# Driver.net
KiCad netlist of a schematic drawn in Altium Designer
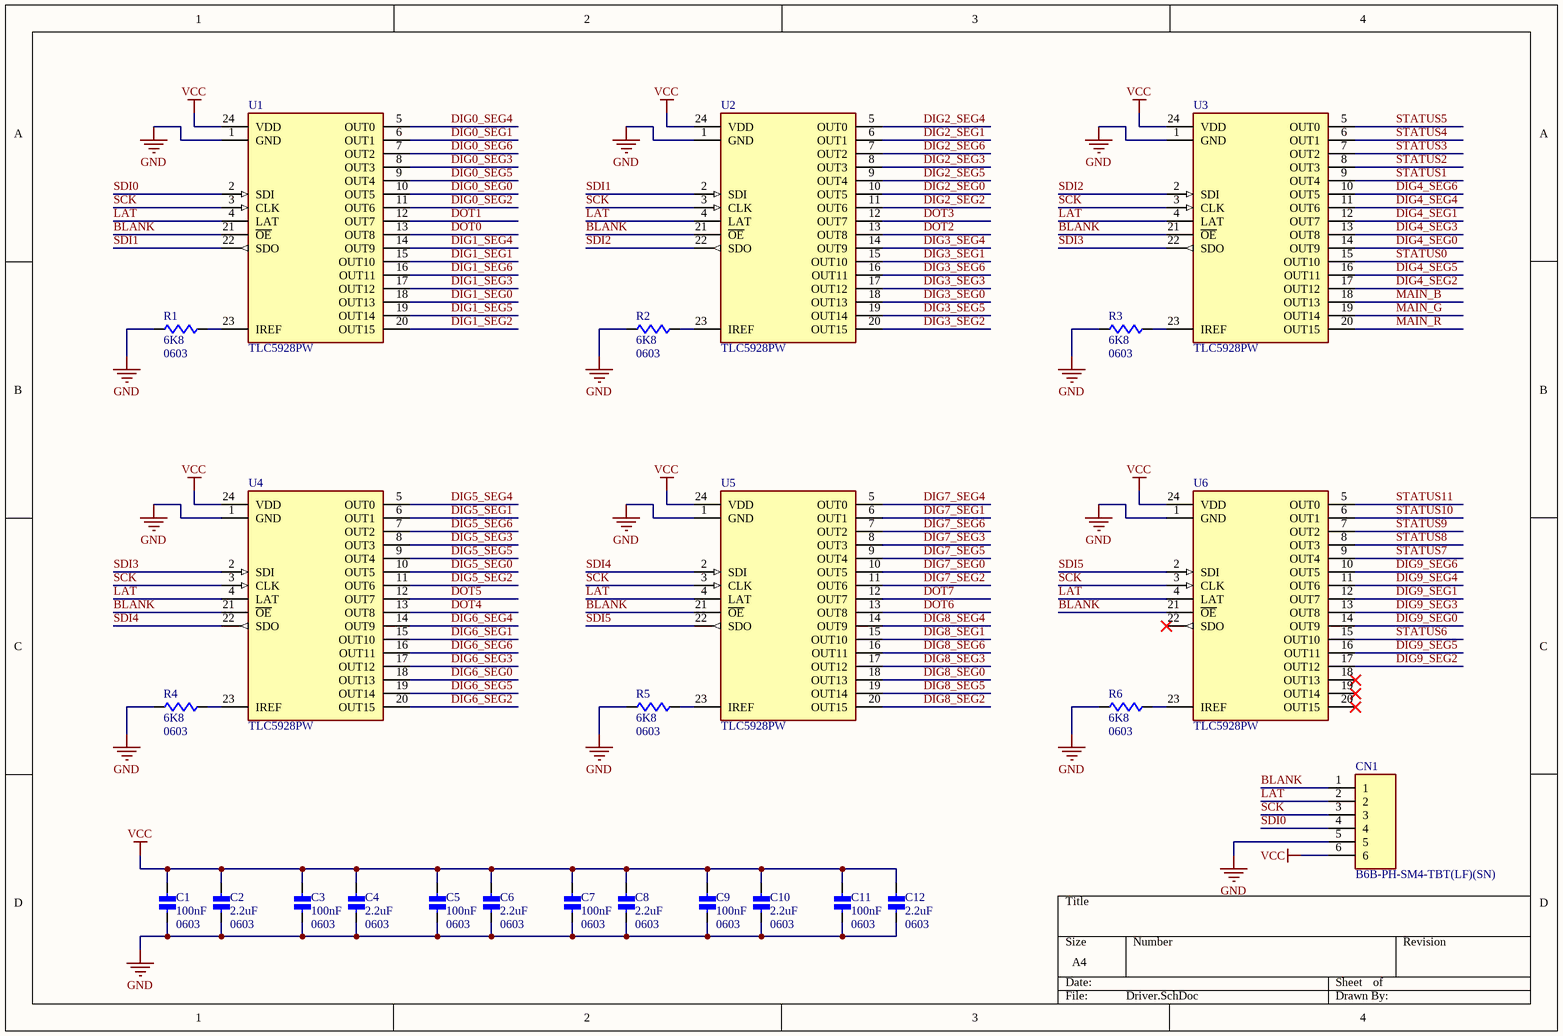
[diagram p0: Driver.SchDoc]

(export (version "E")
  (design (tool "Eeschema 10.0.6"))
  (components
    (comp (ref "C1")
      (value "100nF")
      (footprint "CAPC0603X08N")
      (description "Generic 0603 Capacitors")
      (fields (field (name "PACKAGE") "0603"))
      (libsource (lib "Chess Clock Front Display") (part "GENERIC CAPC 0603"))
    )
    (comp (ref "C2")
      (value "2.2uF")
      (footprint "CAPC0603X08N")
      (description "Generic 0603 Capacitors")
      (fields (field (name "PACKAGE") "0603"))
      (libsource (lib "Chess Clock Front Display") (part "GENERIC CAPC 0603"))
    )
    (comp (ref "C3")
      (value "100nF")
      (footprint "CAPC0603X08N")
      (description "Generic 0603 Capacitors")
      (fields (field (name "PACKAGE") "0603"))
      (libsource (lib "Chess Clock Front Display") (part "GENERIC CAPC 0603"))
    )
    (comp (ref "C4")
      (value "2.2uF")
      (footprint "CAPC0603X08N")
      (description "Generic 0603 Capacitors")
      (fields (field (name "PACKAGE") "0603"))
      (libsource (lib "Chess Clock Front Display") (part "GENERIC CAPC 0603"))
    )
    (comp (ref "C5")
      (value "100nF")
      (footprint "CAPC0603X08N")
      (description "Generic 0603 Capacitors")
      (fields (field (name "PACKAGE") "0603"))
      (libsource (lib "Chess Clock Front Display") (part "GENERIC CAPC 0603"))
    )
    (comp (ref "C6")
      (value "2.2uF")
      (footprint "CAPC0603X08N")
      (description "Generic 0603 Capacitors")
      (fields (field (name "PACKAGE") "0603"))
      (libsource (lib "Chess Clock Front Display") (part "GENERIC CAPC 0603"))
    )
    (comp (ref "C7")
      (value "100nF")
      (footprint "CAPC0603X08N")
      (description "Generic 0603 Capacitors")
      (fields (field (name "PACKAGE") "0603"))
      (libsource (lib "Chess Clock Front Display") (part "GENERIC CAPC 0603"))
    )
    (comp (ref "C8")
      (value "2.2uF")
      (footprint "CAPC0603X08N")
      (description "Generic 0603 Capacitors")
      (fields (field (name "PACKAGE") "0603"))
      (libsource (lib "Chess Clock Front Display") (part "GENERIC CAPC 0603"))
    )
    (comp (ref "C9")
      (value "100nF")
      (footprint "CAPC0603X08N")
      (description "Generic 0603 Capacitors")
      (fields (field (name "PACKAGE") "0603"))
      (libsource (lib "Chess Clock Front Display") (part "GENERIC CAPC 0603"))
    )
    (comp (ref "C10")
      (value "2.2uF")
      (footprint "CAPC0603X08N")
      (description "Generic 0603 Capacitors")
      (fields (field (name "PACKAGE") "0603"))
      (libsource (lib "Chess Clock Front Display") (part "GENERIC CAPC 0603"))
    )
    (comp (ref "C11")
      (value "100nF")
      (footprint "CAPC0603X08N")
      (description "Generic 0603 Capacitors")
      (fields (field (name "PACKAGE") "0603"))
      (libsource (lib "Chess Clock Front Display") (part "GENERIC CAPC 0603"))
    )
    (comp (ref "C12")
      (value "2.2uF")
      (footprint "CAPC0603X08N")
      (description "Generic 0603 Capacitors")
      (fields (field (name "PACKAGE") "0603"))
      (libsource (lib "Chess Clock Front Display") (part "GENERIC CAPC 0603"))
    )
    (comp (ref "CN1")
      (value "B6B-PH-SM4-TBT(LF)(SN)")
      (footprint "B6B-PH-SM4-TBT(LF)(SN)")
      (description "Connector Header Surface Mount 6 position 0.079\" (2.00mm)")
      (libsource (lib "Chess Clock Front Display") (part "B6B-PH-SM4-TBT(LF)(SN)"))
    )
    (comp (ref "R1")
      (value "6K8")
      (footprint "RESC0603X04N")
      (description "Generic 0603 1%/5% Resistor")
      (fields (field (name "PACKAGE") "0603"))
      (libsource (lib "Chess Clock Front Display") (part "GENERIC RESC 0603"))
    )
    (comp (ref "R2")
      (value "6K8")
      (footprint "RESC0603X04N")
      (description "Generic 0603 1%/5% Resistor")
      (fields (field (name "PACKAGE") "0603"))
      (libsource (lib "Chess Clock Front Display") (part "GENERIC RESC 0603"))
    )
    (comp (ref "R3")
      (value "6K8")
      (footprint "RESC0603X04N")
      (description "Generic 0603 1%/5% Resistor")
      (fields (field (name "PACKAGE") "0603"))
      (libsource (lib "Chess Clock Front Display") (part "GENERIC RESC 0603"))
    )
    (comp (ref "R4")
      (value "6K8")
      (footprint "RESC0603X04N")
      (description "Generic 0603 1%/5% Resistor")
      (fields (field (name "PACKAGE") "0603"))
      (libsource (lib "Chess Clock Front Display") (part "GENERIC RESC 0603"))
    )
    (comp (ref "R5")
      (value "6K8")
      (footprint "RESC0603X04N")
      (description "Generic 0603 1%/5% Resistor")
      (fields (field (name "PACKAGE") "0603"))
      (libsource (lib "Chess Clock Front Display") (part "GENERIC RESC 0603"))
    )
    (comp (ref "R6")
      (value "6K8")
      (footprint "RESC0603X04N")
      (description "Generic 0603 1%/5% Resistor")
      (fields (field (name "PACKAGE") "0603"))
      (libsource (lib "Chess Clock Front Display") (part "GENERIC RESC 0603"))
    )
    (comp (ref "U1")
      (value "TLC5928PW")
      (footprint "TSOP65P640X120-24N")
      (description "LED Driver IC 16 Output Linear Shift Register  Dimming 35mA 24-TSSOP")
      (fields (field (name "MANUFACTURER") "Texas Instruments"))
      (libsource (lib "Chess Clock Front Display") (part "TLC5928PW"))
    )
    (comp (ref "U2")
      (value "TLC5928PW")
      (footprint "TSOP65P640X120-24N")
      (description "LED Driver IC 16 Output Linear Shift Register  Dimming 35mA 24-TSSOP")
      (fields (field (name "MANUFACTURER") "Texas Instruments"))
      (libsource (lib "Chess Clock Front Display") (part "TLC5928PW"))
    )
    (comp (ref "U3")
      (value "TLC5928PW")
      (footprint "TSOP65P640X120-24N")
      (description "LED Driver IC 16 Output Linear Shift Register  Dimming 35mA 24-TSSOP")
      (fields (field (name "MANUFACTURER") "Texas Instruments"))
      (libsource (lib "Chess Clock Front Display") (part "TLC5928PW"))
    )
    (comp (ref "U4")
      (value "TLC5928PW")
      (footprint "TSOP65P640X120-24N")
      (description "LED Driver IC 16 Output Linear Shift Register  Dimming 35mA 24-TSSOP")
      (fields (field (name "MANUFACTURER") "Texas Instruments"))
      (libsource (lib "Chess Clock Front Display") (part "TLC5928PW"))
    )
    (comp (ref "U5")
      (value "TLC5928PW")
      (footprint "TSOP65P640X120-24N")
      (description "LED Driver IC 16 Output Linear Shift Register  Dimming 35mA 24-TSSOP")
      (fields (field (name "MANUFACTURER") "Texas Instruments"))
      (libsource (lib "Chess Clock Front Display") (part "TLC5928PW"))
    )
    (comp (ref "U6")
      (value "TLC5928PW")
      (footprint "TSOP65P640X120-24N")
      (description "LED Driver IC 16 Output Linear Shift Register  Dimming 35mA 24-TSSOP")
      (fields (field (name "MANUFACTURER") "Texas Instruments"))
      (libsource (lib "Chess Clock Front Display") (part "TLC5928PW"))
    )
  )
  (nets
    (net (code "1") (name "/BLANK") (class "Default")
      (node (ref "CN1") (pin "1") (pinfunction "1_1") (pintype "passive"))
      (node (ref "U1") (pin "21") (pinfunction "~{OE}_21") (pintype "passive"))
      (node (ref "U2") (pin "21") (pinfunction "~{OE}_21") (pintype "passive"))
      (node (ref "U3") (pin "21") (pinfunction "~{OE}_21") (pintype "passive"))
      (node (ref "U4") (pin "21") (pinfunction "~{OE}_21") (pintype "passive"))
      (node (ref "U5") (pin "21") (pinfunction "~{OE}_21") (pintype "passive"))
      (node (ref "U6") (pin "21") (pinfunction "~{OE}_21") (pintype "passive"))
    )
    (net (code "2") (name "/DIG0_SEG0") (class "Default")
      (node (ref "U1") (pin "10") (pinfunction "OUT5_10") (pintype "passive"))
    )
    (net (code "3") (name "/DIG0_SEG1") (class "Default")
      (node (ref "U1") (pin "6") (pinfunction "OUT1_6") (pintype "passive"))
    )
    (net (code "4") (name "/DIG0_SEG2") (class "Default")
      (node (ref "U1") (pin "11") (pinfunction "OUT6_11") (pintype "passive"))
    )
    (net (code "5") (name "/DIG0_SEG3") (class "Default")
      (node (ref "U1") (pin "8") (pinfunction "OUT3_8") (pintype "passive"))
    )
    (net (code "6") (name "/DIG0_SEG4") (class "Default")
      (node (ref "U1") (pin "5") (pinfunction "OUT0_5") (pintype "passive"))
    )
    (net (code "7") (name "/DIG0_SEG5") (class "Default")
      (node (ref "U1") (pin "9") (pinfunction "OUT4_9") (pintype "passive"))
    )
    (net (code "8") (name "/DIG0_SEG6") (class "Default")
      (node (ref "U1") (pin "7") (pinfunction "OUT2_7") (pintype "passive"))
    )
    (net (code "9") (name "/DIG1_SEG0") (class "Default")
      (node (ref "U1") (pin "18") (pinfunction "OUT13_18") (pintype "passive"))
    )
    (net (code "10") (name "/DIG1_SEG1") (class "Default")
      (node (ref "U1") (pin "15") (pinfunction "OUT10_15") (pintype "passive"))
    )
    (net (code "11") (name "/DIG1_SEG2") (class "Default")
      (node (ref "U1") (pin "20") (pinfunction "OUT15_20") (pintype "passive"))
    )
    (net (code "12") (name "/DIG1_SEG3") (class "Default")
      (node (ref "U1") (pin "17") (pinfunction "OUT12_17") (pintype "passive"))
    )
    (net (code "13") (name "/DIG1_SEG4") (class "Default")
      (node (ref "U1") (pin "14") (pinfunction "OUT9_14") (pintype "passive"))
    )
    (net (code "14") (name "/DIG1_SEG5") (class "Default")
      (node (ref "U1") (pin "19") (pinfunction "OUT14_19") (pintype "passive"))
    )
    (net (code "15") (name "/DIG1_SEG6") (class "Default")
      (node (ref "U1") (pin "16") (pinfunction "OUT11_16") (pintype "passive"))
    )
    (net (code "16") (name "/DIG2_SEG0") (class "Default")
      (node (ref "U2") (pin "10") (pinfunction "OUT5_10") (pintype "passive"))
    )
    (net (code "17") (name "/DIG2_SEG1") (class "Default")
      (node (ref "U2") (pin "6") (pinfunction "OUT1_6") (pintype "passive"))
    )
    (net (code "18") (name "/DIG2_SEG2") (class "Default")
      (node (ref "U2") (pin "11") (pinfunction "OUT6_11") (pintype "passive"))
    )
    (net (code "19") (name "/DIG2_SEG3") (class "Default")
      (node (ref "U2") (pin "8") (pinfunction "OUT3_8") (pintype "passive"))
    )
    (net (code "20") (name "/DIG2_SEG4") (class "Default")
      (node (ref "U2") (pin "5") (pinfunction "OUT0_5") (pintype "passive"))
    )
    (net (code "21") (name "/DIG2_SEG5") (class "Default")
      (node (ref "U2") (pin "9") (pinfunction "OUT4_9") (pintype "passive"))
    )
    (net (code "22") (name "/DIG2_SEG6") (class "Default")
      (node (ref "U2") (pin "7") (pinfunction "OUT2_7") (pintype "passive"))
    )
    (net (code "23") (name "/DIG3_SEG0") (class "Default")
      (node (ref "U2") (pin "18") (pinfunction "OUT13_18") (pintype "passive"))
    )
    (net (code "24") (name "/DIG3_SEG1") (class "Default")
      (node (ref "U2") (pin "15") (pinfunction "OUT10_15") (pintype "passive"))
    )
    (net (code "25") (name "/DIG3_SEG2") (class "Default")
      (node (ref "U2") (pin "20") (pinfunction "OUT15_20") (pintype "passive"))
    )
    (net (code "26") (name "/DIG3_SEG3") (class "Default")
      (node (ref "U2") (pin "17") (pinfunction "OUT12_17") (pintype "passive"))
    )
    (net (code "27") (name "/DIG3_SEG4") (class "Default")
      (node (ref "U2") (pin "14") (pinfunction "OUT9_14") (pintype "passive"))
    )
    (net (code "28") (name "/DIG3_SEG5") (class "Default")
      (node (ref "U2") (pin "19") (pinfunction "OUT14_19") (pintype "passive"))
    )
    (net (code "29") (name "/DIG3_SEG6") (class "Default")
      (node (ref "U2") (pin "16") (pinfunction "OUT11_16") (pintype "passive"))
    )
    (net (code "30") (name "/DIG4_SEG0") (class "Default")
      (node (ref "U3") (pin "14") (pinfunction "OUT9_14") (pintype "passive"))
    )
    (net (code "31") (name "/DIG4_SEG1") (class "Default")
      (node (ref "U3") (pin "12") (pinfunction "OUT7_12") (pintype "passive"))
    )
    (net (code "32") (name "/DIG4_SEG2") (class "Default")
      (node (ref "U3") (pin "17") (pinfunction "OUT12_17") (pintype "passive"))
    )
    (net (code "33") (name "/DIG4_SEG3") (class "Default")
      (node (ref "U3") (pin "13") (pinfunction "OUT8_13") (pintype "passive"))
    )
    (net (code "34") (name "/DIG4_SEG4") (class "Default")
      (node (ref "U3") (pin "11") (pinfunction "OUT6_11") (pintype "passive"))
    )
    (net (code "35") (name "/DIG4_SEG5") (class "Default")
      (node (ref "U3") (pin "16") (pinfunction "OUT11_16") (pintype "passive"))
    )
    (net (code "36") (name "/DIG4_SEG6") (class "Default")
      (node (ref "U3") (pin "10") (pinfunction "OUT5_10") (pintype "passive"))
    )
    (net (code "37") (name "/DIG5_SEG0") (class "Default")
      (node (ref "U4") (pin "10") (pinfunction "OUT5_10") (pintype "passive"))
    )
    (net (code "38") (name "/DIG5_SEG1") (class "Default")
      (node (ref "U4") (pin "6") (pinfunction "OUT1_6") (pintype "passive"))
    )
    (net (code "39") (name "/DIG5_SEG2") (class "Default")
      (node (ref "U4") (pin "11") (pinfunction "OUT6_11") (pintype "passive"))
    )
    (net (code "40") (name "/DIG5_SEG3") (class "Default")
      (node (ref "U4") (pin "8") (pinfunction "OUT3_8") (pintype "passive"))
    )
    (net (code "41") (name "/DIG5_SEG4") (class "Default")
      (node (ref "U4") (pin "5") (pinfunction "OUT0_5") (pintype "passive"))
    )
    (net (code "42") (name "/DIG5_SEG5") (class "Default")
      (node (ref "U4") (pin "9") (pinfunction "OUT4_9") (pintype "passive"))
    )
    (net (code "43") (name "/DIG5_SEG6") (class "Default")
      (node (ref "U4") (pin "7") (pinfunction "OUT2_7") (pintype "passive"))
    )
    (net (code "44") (name "/DIG6_SEG0") (class "Default")
      (node (ref "U4") (pin "18") (pinfunction "OUT13_18") (pintype "passive"))
    )
    (net (code "45") (name "/DIG6_SEG1") (class "Default")
      (node (ref "U4") (pin "15") (pinfunction "OUT10_15") (pintype "passive"))
    )
    (net (code "46") (name "/DIG6_SEG2") (class "Default")
      (node (ref "U4") (pin "20") (pinfunction "OUT15_20") (pintype "passive"))
    )
    (net (code "47") (name "/DIG6_SEG3") (class "Default")
      (node (ref "U4") (pin "17") (pinfunction "OUT12_17") (pintype "passive"))
    )
    (net (code "48") (name "/DIG6_SEG4") (class "Default")
      (node (ref "U4") (pin "14") (pinfunction "OUT9_14") (pintype "passive"))
    )
    (net (code "49") (name "/DIG6_SEG5") (class "Default")
      (node (ref "U4") (pin "19") (pinfunction "OUT14_19") (pintype "passive"))
    )
    (net (code "50") (name "/DIG6_SEG6") (class "Default")
      (node (ref "U4") (pin "16") (pinfunction "OUT11_16") (pintype "passive"))
    )
    (net (code "51") (name "/DIG7_SEG0") (class "Default")
      (node (ref "U5") (pin "10") (pinfunction "OUT5_10") (pintype "passive"))
    )
    (net (code "52") (name "/DIG7_SEG1") (class "Default")
      (node (ref "U5") (pin "6") (pinfunction "OUT1_6") (pintype "passive"))
    )
    (net (code "53") (name "/DIG7_SEG2") (class "Default")
      (node (ref "U5") (pin "11") (pinfunction "OUT6_11") (pintype "passive"))
    )
    (net (code "54") (name "/DIG7_SEG3") (class "Default")
      (node (ref "U5") (pin "8") (pinfunction "OUT3_8") (pintype "passive"))
    )
    (net (code "55") (name "/DIG7_SEG4") (class "Default")
      (node (ref "U5") (pin "5") (pinfunction "OUT0_5") (pintype "passive"))
    )
    (net (code "56") (name "/DIG7_SEG5") (class "Default")
      (node (ref "U5") (pin "9") (pinfunction "OUT4_9") (pintype "passive"))
    )
    (net (code "57") (name "/DIG7_SEG6") (class "Default")
      (node (ref "U5") (pin "7") (pinfunction "OUT2_7") (pintype "passive"))
    )
    (net (code "58") (name "/DIG8_SEG0") (class "Default")
      (node (ref "U5") (pin "18") (pinfunction "OUT13_18") (pintype "passive"))
    )
    (net (code "59") (name "/DIG8_SEG1") (class "Default")
      (node (ref "U5") (pin "15") (pinfunction "OUT10_15") (pintype "passive"))
    )
    (net (code "60") (name "/DIG8_SEG2") (class "Default")
      (node (ref "U5") (pin "20") (pinfunction "OUT15_20") (pintype "passive"))
    )
    (net (code "61") (name "/DIG8_SEG3") (class "Default")
      (node (ref "U5") (pin "17") (pinfunction "OUT12_17") (pintype "passive"))
    )
    (net (code "62") (name "/DIG8_SEG4") (class "Default")
      (node (ref "U5") (pin "14") (pinfunction "OUT9_14") (pintype "passive"))
    )
    (net (code "63") (name "/DIG8_SEG5") (class "Default")
      (node (ref "U5") (pin "19") (pinfunction "OUT14_19") (pintype "passive"))
    )
    (net (code "64") (name "/DIG8_SEG6") (class "Default")
      (node (ref "U5") (pin "16") (pinfunction "OUT11_16") (pintype "passive"))
    )
    (net (code "65") (name "/DIG9_SEG0") (class "Default")
      (node (ref "U6") (pin "14") (pinfunction "OUT9_14") (pintype "passive"))
    )
    (net (code "66") (name "/DIG9_SEG1") (class "Default")
      (node (ref "U6") (pin "12") (pinfunction "OUT7_12") (pintype "passive"))
    )
    (net (code "67") (name "/DIG9_SEG2") (class "Default")
      (node (ref "U6") (pin "17") (pinfunction "OUT12_17") (pintype "passive"))
    )
    (net (code "68") (name "/DIG9_SEG3") (class "Default")
      (node (ref "U6") (pin "13") (pinfunction "OUT8_13") (pintype "passive"))
    )
    (net (code "69") (name "/DIG9_SEG4") (class "Default")
      (node (ref "U6") (pin "11") (pinfunction "OUT6_11") (pintype "passive"))
    )
    (net (code "70") (name "/DIG9_SEG5") (class "Default")
      (node (ref "U6") (pin "16") (pinfunction "OUT11_16") (pintype "passive"))
    )
    (net (code "71") (name "/DIG9_SEG6") (class "Default")
      (node (ref "U6") (pin "10") (pinfunction "OUT5_10") (pintype "passive"))
    )
    (net (code "72") (name "/DOT0") (class "Default")
      (node (ref "U1") (pin "13") (pinfunction "OUT8_13") (pintype "passive"))
    )
    (net (code "73") (name "/DOT1") (class "Default")
      (node (ref "U1") (pin "12") (pinfunction "OUT7_12") (pintype "passive"))
    )
    (net (code "74") (name "/DOT2") (class "Default")
      (node (ref "U2") (pin "13") (pinfunction "OUT8_13") (pintype "passive"))
    )
    (net (code "75") (name "/DOT3") (class "Default")
      (node (ref "U2") (pin "12") (pinfunction "OUT7_12") (pintype "passive"))
    )
    (net (code "76") (name "/DOT4") (class "Default")
      (node (ref "U4") (pin "13") (pinfunction "OUT8_13") (pintype "passive"))
    )
    (net (code "77") (name "/DOT5") (class "Default")
      (node (ref "U4") (pin "12") (pinfunction "OUT7_12") (pintype "passive"))
    )
    (net (code "78") (name "/DOT6") (class "Default")
      (node (ref "U5") (pin "13") (pinfunction "OUT8_13") (pintype "passive"))
    )
    (net (code "79") (name "/DOT7") (class "Default")
      (node (ref "U5") (pin "12") (pinfunction "OUT7_12") (pintype "passive"))
    )
    (net (code "80") (name "/LAT") (class "Default")
      (node (ref "CN1") (pin "2") (pinfunction "2_2") (pintype "passive"))
      (node (ref "U1") (pin "4") (pinfunction "LAT_4") (pintype "passive"))
      (node (ref "U2") (pin "4") (pinfunction "LAT_4") (pintype "passive"))
      (node (ref "U3") (pin "4") (pinfunction "LAT_4") (pintype "passive"))
      (node (ref "U4") (pin "4") (pinfunction "LAT_4") (pintype "passive"))
      (node (ref "U5") (pin "4") (pinfunction "LAT_4") (pintype "passive"))
      (node (ref "U6") (pin "4") (pinfunction "LAT_4") (pintype "passive"))
    )
    (net (code "81") (name "/MAIN_B") (class "Default")
      (node (ref "U3") (pin "18") (pinfunction "OUT13_18") (pintype "passive"))
    )
    (net (code "82") (name "/MAIN_G") (class "Default")
      (node (ref "U3") (pin "19") (pinfunction "OUT14_19") (pintype "passive"))
    )
    (net (code "83") (name "/MAIN_R") (class "Default")
      (node (ref "U3") (pin "20") (pinfunction "OUT15_20") (pintype "passive"))
    )
    (net (code "84") (name "/SCK") (class "Default")
      (node (ref "CN1") (pin "3") (pinfunction "3_3") (pintype "passive"))
      (node (ref "U1") (pin "3") (pinfunction "CLK_3") (pintype "input"))
      (node (ref "U2") (pin "3") (pinfunction "CLK_3") (pintype "input"))
      (node (ref "U3") (pin "3") (pinfunction "CLK_3") (pintype "input"))
      (node (ref "U4") (pin "3") (pinfunction "CLK_3") (pintype "input"))
      (node (ref "U5") (pin "3") (pinfunction "CLK_3") (pintype "input"))
      (node (ref "U6") (pin "3") (pinfunction "CLK_3") (pintype "input"))
    )
    (net (code "85") (name "/SDI0") (class "Default")
      (node (ref "CN1") (pin "4") (pinfunction "4_4") (pintype "passive"))
      (node (ref "U1") (pin "2") (pinfunction "SDI_2") (pintype "input"))
    )
    (net (code "86") (name "/SDI1") (class "Default")
      (node (ref "U1") (pin "22") (pinfunction "SDO_22") (pintype "output"))
      (node (ref "U2") (pin "2") (pinfunction "SDI_2") (pintype "input"))
    )
    (net (code "87") (name "/SDI2") (class "Default")
      (node (ref "U2") (pin "22") (pinfunction "SDO_22") (pintype "output"))
      (node (ref "U3") (pin "2") (pinfunction "SDI_2") (pintype "input"))
    )
    (net (code "88") (name "/SDI3") (class "Default")
      (node (ref "U3") (pin "22") (pinfunction "SDO_22") (pintype "output"))
      (node (ref "U4") (pin "2") (pinfunction "SDI_2") (pintype "input"))
    )
    (net (code "89") (name "/SDI4") (class "Default")
      (node (ref "U4") (pin "22") (pinfunction "SDO_22") (pintype "output"))
      (node (ref "U5") (pin "2") (pinfunction "SDI_2") (pintype "input"))
    )
    (net (code "90") (name "/SDI5") (class "Default")
      (node (ref "U5") (pin "22") (pinfunction "SDO_22") (pintype "output"))
      (node (ref "U6") (pin "2") (pinfunction "SDI_2") (pintype "input"))
    )
    (net (code "91") (name "/STATUS0") (class "Default")
      (node (ref "U3") (pin "15") (pinfunction "OUT10_15") (pintype "passive"))
    )
    (net (code "92") (name "/STATUS1") (class "Default")
      (node (ref "U3") (pin "9") (pinfunction "OUT4_9") (pintype "passive"))
    )
    (net (code "93") (name "/STATUS2") (class "Default")
      (node (ref "U3") (pin "8") (pinfunction "OUT3_8") (pintype "passive"))
    )
    (net (code "94") (name "/STATUS3") (class "Default")
      (node (ref "U3") (pin "7") (pinfunction "OUT2_7") (pintype "passive"))
    )
    (net (code "95") (name "/STATUS4") (class "Default")
      (node (ref "U3") (pin "6") (pinfunction "OUT1_6") (pintype "passive"))
    )
    (net (code "96") (name "/STATUS5") (class "Default")
      (node (ref "U3") (pin "5") (pinfunction "OUT0_5") (pintype "passive"))
    )
    (net (code "97") (name "/STATUS6") (class "Default")
      (node (ref "U6") (pin "15") (pinfunction "OUT10_15") (pintype "passive"))
    )
    (net (code "98") (name "/STATUS7") (class "Default")
      (node (ref "U6") (pin "9") (pinfunction "OUT4_9") (pintype "passive"))
    )
    (net (code "99") (name "/STATUS8") (class "Default")
      (node (ref "U6") (pin "8") (pinfunction "OUT3_8") (pintype "passive"))
    )
    (net (code "100") (name "/STATUS9") (class "Default")
      (node (ref "U6") (pin "7") (pinfunction "OUT2_7") (pintype "passive"))
    )
    (net (code "101") (name "/STATUS10") (class "Default")
      (node (ref "U6") (pin "6") (pinfunction "OUT1_6") (pintype "passive"))
    )
    (net (code "102") (name "/STATUS11") (class "Default")
      (node (ref "U6") (pin "5") (pinfunction "OUT0_5") (pintype "passive"))
    )
    (net (code "103") (name "GND") (class "Default")
      (node (ref "C1") (pin "2") (pinfunction "2_2") (pintype "passive"))
      (node (ref "C10") (pin "2") (pinfunction "2_2") (pintype "passive"))
      (node (ref "C11") (pin "2") (pinfunction "2_2") (pintype "passive"))
      (node (ref "C12") (pin "2") (pinfunction "2_2") (pintype "passive"))
      (node (ref "C2") (pin "2") (pinfunction "2_2") (pintype "passive"))
      (node (ref "C3") (pin "2") (pinfunction "2_2") (pintype "passive"))
      (node (ref "C4") (pin "2") (pinfunction "2_2") (pintype "passive"))
      (node (ref "C5") (pin "2") (pinfunction "2_2") (pintype "passive"))
      (node (ref "C6") (pin "2") (pinfunction "2_2") (pintype "passive"))
      (node (ref "C7") (pin "2") (pinfunction "2_2") (pintype "passive"))
      (node (ref "C8") (pin "2") (pinfunction "2_2") (pintype "passive"))
      (node (ref "C9") (pin "2") (pinfunction "2_2") (pintype "passive"))
      (node (ref "CN1") (pin "5") (pinfunction "5_5") (pintype "passive"))
      (node (ref "R1") (pin "2") (pinfunction "2_2") (pintype "passive"))
      (node (ref "R2") (pin "2") (pinfunction "2_2") (pintype "passive"))
      (node (ref "R3") (pin "2") (pinfunction "2_2") (pintype "passive"))
      (node (ref "R4") (pin "2") (pinfunction "2_2") (pintype "passive"))
      (node (ref "R5") (pin "2") (pinfunction "2_2") (pintype "passive"))
      (node (ref "R6") (pin "2") (pinfunction "2_2") (pintype "passive"))
      (node (ref "U1") (pin "1") (pinfunction "GND_1") (pintype "passive"))
      (node (ref "U2") (pin "1") (pinfunction "GND_1") (pintype "passive"))
      (node (ref "U3") (pin "1") (pinfunction "GND_1") (pintype "passive"))
      (node (ref "U4") (pin "1") (pinfunction "GND_1") (pintype "passive"))
      (node (ref "U5") (pin "1") (pinfunction "GND_1") (pintype "passive"))
      (node (ref "U6") (pin "1") (pinfunction "GND_1") (pintype "passive"))
    )
    (net (code "104") (name "Net-(U1-IREF)") (class "Default")
      (node (ref "R1") (pin "1") (pinfunction "1_1") (pintype "passive"))
      (node (ref "U1") (pin "23") (pinfunction "IREF_23") (pintype "passive"))
    )
    (net (code "105") (name "Net-(U2-IREF)") (class "Default")
      (node (ref "R2") (pin "1") (pinfunction "1_1") (pintype "passive"))
      (node (ref "U2") (pin "23") (pinfunction "IREF_23") (pintype "passive"))
    )
    (net (code "106") (name "Net-(U3-IREF)") (class "Default")
      (node (ref "R3") (pin "1") (pinfunction "1_1") (pintype "passive"))
      (node (ref "U3") (pin "23") (pinfunction "IREF_23") (pintype "passive"))
    )
    (net (code "107") (name "Net-(U4-IREF)") (class "Default")
      (node (ref "R4") (pin "1") (pinfunction "1_1") (pintype "passive"))
      (node (ref "U4") (pin "23") (pinfunction "IREF_23") (pintype "passive"))
    )
    (net (code "108") (name "Net-(U5-IREF)") (class "Default")
      (node (ref "R5") (pin "1") (pinfunction "1_1") (pintype "passive"))
      (node (ref "U5") (pin "23") (pinfunction "IREF_23") (pintype "passive"))
    )
    (net (code "109") (name "Net-(U6-IREF)") (class "Default")
      (node (ref "R6") (pin "1") (pinfunction "1_1") (pintype "passive"))
      (node (ref "U6") (pin "23") (pinfunction "IREF_23") (pintype "passive"))
    )
    (net (code "110") (name "VCC") (class "Default")
      (node (ref "C1") (pin "1") (pinfunction "1_1") (pintype "passive"))
      (node (ref "C10") (pin "1") (pinfunction "1_1") (pintype "passive"))
      (node (ref "C11") (pin "1") (pinfunction "1_1") (pintype "passive"))
      (node (ref "C12") (pin "1") (pinfunction "1_1") (pintype "passive"))
      (node (ref "C2") (pin "1") (pinfunction "1_1") (pintype "passive"))
      (node (ref "C3") (pin "1") (pinfunction "1_1") (pintype "passive"))
      (node (ref "C4") (pin "1") (pinfunction "1_1") (pintype "passive"))
      (node (ref "C5") (pin "1") (pinfunction "1_1") (pintype "passive"))
      (node (ref "C6") (pin "1") (pinfunction "1_1") (pintype "passive"))
      (node (ref "C7") (pin "1") (pinfunction "1_1") (pintype "passive"))
      (node (ref "C8") (pin "1") (pinfunction "1_1") (pintype "passive"))
      (node (ref "C9") (pin "1") (pinfunction "1_1") (pintype "passive"))
      (node (ref "CN1") (pin "6") (pinfunction "6_6") (pintype "passive"))
      (node (ref "U1") (pin "24") (pinfunction "VDD_24") (pintype "passive"))
      (node (ref "U2") (pin "24") (pinfunction "VDD_24") (pintype "passive"))
      (node (ref "U3") (pin "24") (pinfunction "VDD_24") (pintype "passive"))
      (node (ref "U4") (pin "24") (pinfunction "VDD_24") (pintype "passive"))
      (node (ref "U5") (pin "24") (pinfunction "VDD_24") (pintype "passive"))
      (node (ref "U6") (pin "24") (pinfunction "VDD_24") (pintype "passive"))
    )
    (net (code "111") (name "unconnected-(U6-OUT13-Pad18)") (class "Default")
      (node (ref "U6") (pin "18") (pinfunction "OUT13_18") (pintype "passive+no_connect"))
    )
    (net (code "112") (name "unconnected-(U6-OUT14-Pad19)") (class "Default")
      (node (ref "U6") (pin "19") (pinfunction "OUT14_19") (pintype "passive+no_connect"))
    )
    (net (code "113") (name "unconnected-(U6-OUT15-Pad20)") (class "Default")
      (node (ref "U6") (pin "20") (pinfunction "OUT15_20") (pintype "passive+no_connect"))
    )
    (net (code "114") (name "unconnected-(U6-SDO-Pad22)") (class "Default")
      (node (ref "U6") (pin "22") (pinfunction "SDO_22") (pintype "output+no_connect"))
    )
  )
)
